# og22.net
KiCad netlist of a schematic drawn in EAGLE
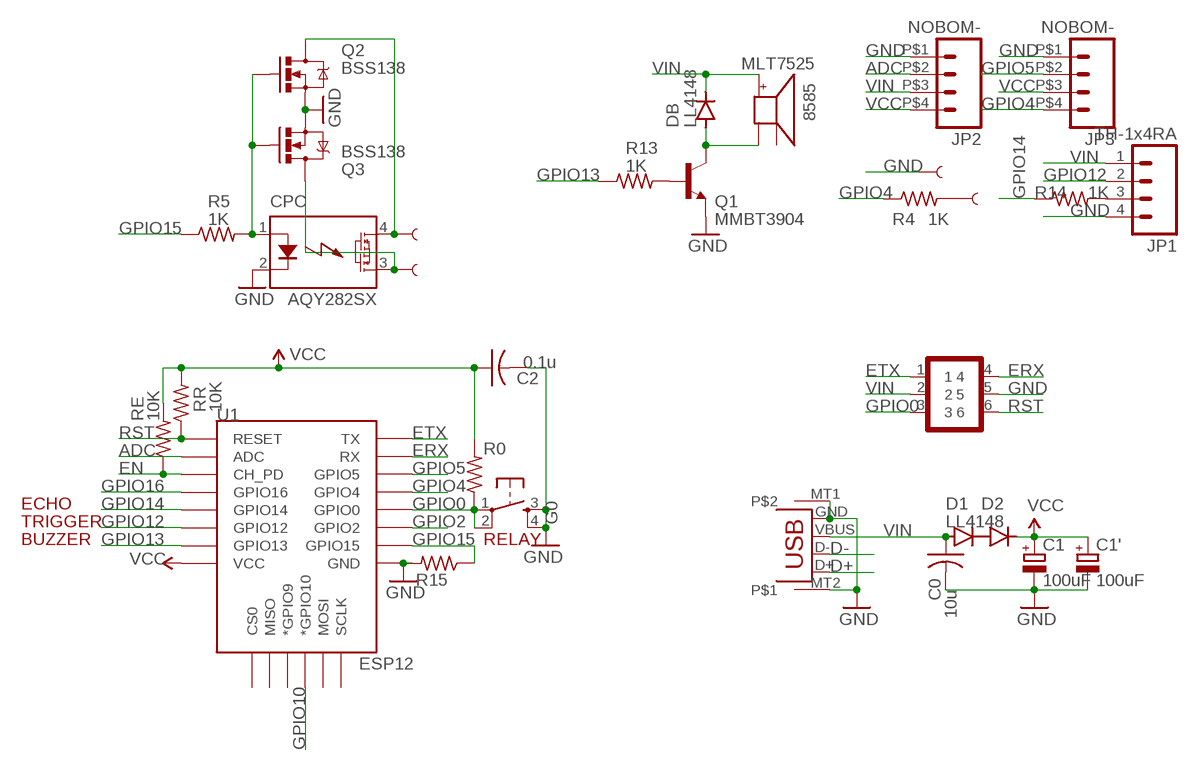
[diagram p0: schematic, sheet 1]

(export (version "E")
  (design (tool "Eeschema 10.0.6"))
  (components
    (comp (ref "8585")
      (value "MLT7525")
      (footprint "eagle-import:SMT-8585-BUZZER")
      (libsource (lib "eagle-import") (part "BUZZER"))
    )
    (comp (ref "C0")
      (value "10u")
      (footprint "eagle-import:C0805K")
      (libsource (lib "eagle-import") (part "C-USC0805K"))
    )
    (comp (ref "C1")
      (value "100uF")
      (footprint "eagle-import:PANASONIC_C")
      (libsource (lib "eagle-import") (part "CPOL-EUC"))
    )
    (comp (ref "C1'")
      (value "100uF")
      (footprint "eagle-import:PANASONIC_C")
      (libsource (lib "eagle-import") (part "CPOL-EUC"))
    )
    (comp (ref "C2")
      (value "0.1u")
      (footprint "eagle-import:C0603K")
      (libsource (lib "eagle-import") (part "C-USC0603K"))
    )
    (comp (ref "CPC")
      (value "AQY282SX")
      (footprint "eagle-import:PHOTOMOS")
      (libsource (lib "eagle-import") (part "AQY282"))
    )
    (comp (ref "D1")
      (value "LL4148")
      (footprint "eagle-import:MINIMELF")
      (libsource (lib "eagle-import") (part "DIODE-MINIMELF"))
    )
    (comp (ref "D2")
      (value "LL4148")
      (footprint "eagle-import:MINIMELF")
      (libsource (lib "eagle-import") (part "DIODE-MINIMELF"))
    )
    (comp (ref "DB")
      (value "LL4148")
      (footprint "eagle-import:MINIMELF")
      (libsource (lib "eagle-import") (part "DIODE-MINIMELF"))
    )
    (comp (ref "G0")
      (value "TH-6x11")
      (footprint "eagle-import:EVQ-Q2")
      (libsource (lib "eagle-import") (part "SPST_TACTEVQQ2"))
    )
    (comp (ref "JP1")
      (value "TH-1x4RA")
      (footprint "eagle-import:1X04_SONICSENSOR_EXT2")
      (libsource (lib "eagle-import") (part "M04EXT2"))
    )
    (comp (ref "JP2")
      (value "NOBOM-")
      (footprint "eagle-import:1X04-2X2")
      (libsource (lib "eagle-import") (part "M042X2"))
    )
    (comp (ref "JP3")
      (value "NOBOM-")
      (footprint "eagle-import:1X04-2X2")
      (libsource (lib "eagle-import") (part "M042X2"))
    )
    (comp (ref "Q1")
      (value "MMBT3904")
      (footprint "eagle-import:SOT23-3")
      (libsource (lib "eagle-import") (part "TRANSISTOR_NPNSOT23-3"))
    )
    (comp (ref "Q2")
      (value "BSS138")
      (footprint "eagle-import:SOT23-3")
      (libsource (lib "eagle-import") (part "MOSFET-NCHANNELSMD"))
    )
    (comp (ref "Q3")
      (value "BSS138")
      (footprint "eagle-import:SOT23-3")
      (libsource (lib "eagle-import") (part "MOSFET-NCHANNELSMD"))
    )
    (comp (ref "R0")
      (value "10K")
      (footprint "eagle-import:R0603")
      (libsource (lib "eagle-import") (part "R-US_R0603"))
    )
    (comp (ref "R4")
      (value "1K")
      (footprint "eagle-import:R0603")
      (libsource (lib "eagle-import") (part "adafruit2013_R-US_R0603"))
    )
    (comp (ref "R5")
      (value "1K")
      (footprint "eagle-import:R0603")
      (libsource (lib "eagle-import") (part "adafruit2013_R-US_R0603"))
    )
    (comp (ref "R13")
      (value "1K")
      (footprint "eagle-import:R0603")
      (libsource (lib "eagle-import") (part "adafruit2013_R-US_R0603"))
    )
    (comp (ref "R14")
      (value "1K")
      (footprint "eagle-import:R0603")
      (libsource (lib "eagle-import") (part "adafruit2013_R-US_R0603"))
    )
    (comp (ref "R15")
      (value "10K")
      (footprint "eagle-import:R0603")
      (libsource (lib "eagle-import") (part "R-US_R0603"))
    )
    (comp (ref "RE")
      (value "10K")
      (footprint "eagle-import:R0603")
      (libsource (lib "eagle-import") (part "R-US_R0603"))
    )
    (comp (ref "RR")
      (value "10K")
      (footprint "eagle-import:R0603")
      (libsource (lib "eagle-import") (part "R-US_R0603"))
    )
    (comp (ref "U$1")
      (value "NOBOM-GF2x3")
      (footprint "eagle-import:GOLDFINGER_2X3")
      (libsource (lib "eagle-import") (part "GOLDFINGER_2X3"))
    )
    (comp (ref "U$2")
      (value "NOBOM-")
      (footprint "eagle-import:PETAL-7MM-DOUBLE")
      (libsource (lib "eagle-import") (part "SEWTAP7MMD"))
    )
    (comp (ref "U$3")
      (value "NOBOM-")
      (footprint "eagle-import:PETAL-7MM-DOUBLE")
      (libsource (lib "eagle-import") (part "SEWTAP7MMD"))
    )
    (comp (ref "U$4")
      (value "NOBOM-")
      (footprint "eagle-import:PETAL-7MM-DOUBLE")
      (libsource (lib "eagle-import") (part "SEWTAP7MMD"))
    )
    (comp (ref "U$5")
      (value "NOBOM-")
      (footprint "eagle-import:PETAL-7MM-DOUBLE")
      (libsource (lib "eagle-import") (part "SEWTAP7MMD"))
    )
    (comp (ref "U1")
      (value "ESP12")
      (footprint "eagle-import:ESP12E-SMD")
      (libsource (lib "eagle-import") (part "ESP12ESMD"))
    )
    (comp (ref "X3")
      (value "MICROXNJ")
      (footprint "eagle-import:USB-MICROB2")
      (libsource (lib "eagle-import") (part "USB+GND"))
    )
  )
  (nets
    (net (code "1") (name "/ADC") (class "Default")
      (node (ref "JP2") (pin "P$2") (pinfunction "2_P$2") (pintype "passive"))
      (node (ref "U1") (pin "ADC") (pinfunction "ADC_ADC") (pintype "bidirectional"))
    )
    (net (code "2") (name "/D+") (class "Default")
      (node (ref "X3") (pin "D+") (pinfunction "D+_D+") (pintype "bidirectional"))
    )
    (net (code "3") (name "/D-") (class "Default")
      (node (ref "X3") (pin "D-") (pinfunction "D-_D-") (pintype "bidirectional"))
    )
    (net (code "4") (name "/EN") (class "Default")
      (node (ref "RE") (pin "1") (pinfunction "1_1") (pintype "passive"))
      (node (ref "U1") (pin "CH_PD") (pinfunction "CH_PD_CH_PD") (pintype "bidirectional"))
    )
    (net (code "5") (name "/ERX") (class "Default")
      (node (ref "U$1") (pin "4") (pinfunction "4_4") (pintype "bidirectional"))
      (node (ref "U1") (pin "RXD0") (pinfunction "RX_RXD0") (pintype "bidirectional"))
    )
    (net (code "6") (name "/ETX") (class "Default")
      (node (ref "U$1") (pin "1") (pinfunction "1_1") (pintype "bidirectional"))
      (node (ref "U1") (pin "TXD0") (pinfunction "TX_TXD0") (pintype "bidirectional"))
    )
    (net (code "7") (name "/GPIO0") (class "Default")
      (node (ref "G0") (pin "1") (pinfunction "1_1") (pintype "passive"))
      (node (ref "G0") (pin "2") (pinfunction "2_2") (pintype "passive"))
      (node (ref "R0") (pin "1") (pinfunction "1_1") (pintype "passive"))
      (node (ref "U$1") (pin "3") (pinfunction "3_3") (pintype "bidirectional"))
      (node (ref "U1") (pin "GPIO0") (pinfunction "GPIO0_GPIO0") (pintype "bidirectional"))
    )
    (net (code "8") (name "/GPIO2") (class "Default")
      (node (ref "U1") (pin "GPIO2") (pinfunction "GPIO2_GPIO2") (pintype "bidirectional"))
    )
    (net (code "9") (name "/GPIO4") (class "Default")
      (node (ref "JP3") (pin "P$4") (pinfunction "4_P$4") (pintype "passive"))
      (node (ref "R4") (pin "1") (pinfunction "1_1") (pintype "passive"))
      (node (ref "U1") (pin "GPIO4") (pinfunction "GPIO4_GPIO4") (pintype "bidirectional"))
    )
    (net (code "10") (name "/GPIO5") (class "Default")
      (node (ref "JP3") (pin "P$2") (pinfunction "2_P$2") (pintype "passive"))
      (node (ref "U1") (pin "GPIO5") (pinfunction "GPIO5_GPIO5") (pintype "bidirectional"))
    )
    (net (code "11") (name "/GPIO10") (class "Default")
      (node (ref "U1") (pin "GPIO10") (pinfunction "*GPIO10_GPIO10") (pintype "bidirectional"))
    )
    (net (code "12") (name "/GPIO12") (class "Default")
      (node (ref "JP1") (pin "2") (pinfunction "2_2") (pintype "passive"))
      (node (ref "U1") (pin "GPIO12") (pinfunction "GPIO12_GPIO12") (pintype "bidirectional"))
    )
    (net (code "13") (name "/GPIO13") (class "Default")
      (node (ref "R13") (pin "1") (pinfunction "1_1") (pintype "passive"))
      (node (ref "U1") (pin "GPIO13") (pinfunction "GPIO13_GPIO13") (pintype "bidirectional"))
    )
    (net (code "14") (name "/GPIO14") (class "Default")
      (node (ref "R14") (pin "1") (pinfunction "1_1") (pintype "passive"))
      (node (ref "U1") (pin "GPIO14") (pinfunction "GPIO14_GPIO14") (pintype "bidirectional"))
    )
    (net (code "15") (name "/GPIO15") (class "Default")
      (node (ref "R15") (pin "1") (pinfunction "1_1") (pintype "passive"))
      (node (ref "R5") (pin "1") (pinfunction "1_1") (pintype "passive"))
      (node (ref "U1") (pin "GPIO15") (pinfunction "GPIO15_GPIO15") (pintype "bidirectional"))
    )
    (net (code "16") (name "/GPIO16") (class "Default")
      (node (ref "U1") (pin "GPIO16") (pinfunction "GPIO16_GPIO16") (pintype "bidirectional"))
    )
    (net (code "17") (name "/RST") (class "Default")
      (node (ref "RR") (pin "1") (pinfunction "1_1") (pintype "passive"))
      (node (ref "U$1") (pin "6") (pinfunction "6_6") (pintype "bidirectional"))
      (node (ref "U1") (pin "RESET") (pinfunction "RESET_RESET") (pintype "bidirectional"))
    )
    (net (code "18") (name "/VIN") (class "Default")
      (node (ref "8585") (pin "+") (pinfunction "+_+") (pintype "passive"))
      (node (ref "C0") (pin "1") (pinfunction "1_1") (pintype "passive"))
      (node (ref "D1") (pin "A") (pinfunction "A_A") (pintype "passive"))
      (node (ref "DB") (pin "C") (pinfunction "C_C") (pintype "passive"))
      (node (ref "JP1") (pin "1") (pinfunction "1_1") (pintype "passive"))
      (node (ref "JP2") (pin "P$3") (pinfunction "3_P$3") (pintype "passive"))
      (node (ref "U$1") (pin "2") (pinfunction "2_2") (pintype "bidirectional"))
      (node (ref "X3") (pin "VBUS") (pinfunction "VBUS_VBUS") (pintype "bidirectional"))
    )
    (net (code "19") (name "GND") (class "Default")
      (node (ref "C0") (pin "2") (pinfunction "2_2") (pintype "passive"))
      (node (ref "C1") (pin "-") (pinfunction "-_-") (pintype "passive"))
      (node (ref "C1'") (pin "-") (pinfunction "-_-") (pintype "passive"))
      (node (ref "C2") (pin "2") (pinfunction "2_2") (pintype "passive"))
      (node (ref "CPC") (pin "2") (pinfunction "K_2") (pintype "passive"))
      (node (ref "G0") (pin "3") (pinfunction "3_3") (pintype "passive"))
      (node (ref "G0") (pin "4") (pinfunction "4_4") (pintype "passive"))
      (node (ref "JP1") (pin "4") (pinfunction "4_4") (pintype "passive"))
      (node (ref "JP2") (pin "P$1") (pinfunction "1_P$1") (pintype "passive"))
      (node (ref "JP3") (pin "P$1") (pinfunction "1_P$1") (pintype "passive"))
      (node (ref "Q1") (pin "2") (pinfunction "E_2") (pintype "passive"))
      (node (ref "Q2") (pin "2") (pinfunction "S_2") (pintype "passive"))
      (node (ref "Q3") (pin "2") (pinfunction "S_2") (pintype "passive"))
      (node (ref "R15") (pin "2") (pinfunction "2_2") (pintype "passive"))
      (node (ref "U$1") (pin "5") (pinfunction "5_5") (pintype "bidirectional"))
      (node (ref "U$4") (pin "P$1") (pinfunction "1_P$1") (pintype "bidirectional"))
      (node (ref "U1") (pin "GND") (pinfunction "GND_GND") (pintype "bidirectional"))
      (node (ref "X3") (pin "GND") (pinfunction "GND_GND") (pintype "bidirectional"))
      (node (ref "X3") (pin "MT1") (pinfunction "P$2_MT1") (pintype "bidirectional"))
      (node (ref "X3") (pin "MT2") (pinfunction "P$1_MT2") (pintype "bidirectional"))
    )
    (net (code "20") (name "Net-(CPC-A)") (class "Default")
      (node (ref "CPC") (pin "1") (pinfunction "A_1") (pintype "passive"))
      (node (ref "Q2") (pin "1") (pinfunction "G_1") (pintype "passive"))
      (node (ref "Q3") (pin "1") (pinfunction "G_1") (pintype "passive"))
      (node (ref "R5") (pin "2") (pinfunction "2_2") (pintype "passive"))
    )
    (net (code "21") (name "Net-(CPC-DS1)") (class "Default")
      (node (ref "CPC") (pin "4") (pinfunction "DS1_4") (pintype "passive"))
      (node (ref "Q2") (pin "3") (pinfunction "D_3") (pintype "passive"))
      (node (ref "U$3") (pin "P$1") (pinfunction "1_P$1") (pintype "bidirectional"))
    )
    (net (code "22") (name "Net-(CPC-DS2)") (class "Default")
      (node (ref "CPC") (pin "3") (pinfunction "DS2_3") (pintype "passive"))
      (node (ref "Q3") (pin "3") (pinfunction "D_3") (pintype "passive"))
      (node (ref "U$2") (pin "P$1") (pinfunction "1_P$1") (pintype "bidirectional"))
    )
    (net (code "23") (name "Net-(D1-PadC)") (class "Default")
      (node (ref "D1") (pin "C") (pinfunction "C_C") (pintype "passive"))
      (node (ref "D2") (pin "A") (pinfunction "A_A") (pintype "passive"))
    )
    (net (code "24") (name "Net-(JP1-Pad3)") (class "Default")
      (node (ref "JP1") (pin "3") (pinfunction "3_3") (pintype "passive"))
      (node (ref "R14") (pin "2") (pinfunction "2_2") (pintype "passive"))
    )
    (net (code "25") (name "Net-(Q1-B)") (class "Default")
      (node (ref "Q1") (pin "1") (pinfunction "B_1") (pintype "passive"))
      (node (ref "R13") (pin "2") (pinfunction "2_2") (pintype "passive"))
    )
    (net (code "26") (name "Net-(Q1-C)") (class "Default")
      (node (ref "8585") (pin "-") (pinfunction "-_-") (pintype "passive"))
      (node (ref "DB") (pin "A") (pinfunction "A_A") (pintype "passive"))
      (node (ref "Q1") (pin "3") (pinfunction "C_3") (pintype "passive"))
    )
    (net (code "27") (name "Net-(U$5-1)") (class "Default")
      (node (ref "R4") (pin "2") (pinfunction "2_2") (pintype "passive"))
      (node (ref "U$5") (pin "P$1") (pinfunction "1_P$1") (pintype "bidirectional"))
    )
    (net (code "28") (name "VCC") (class "Default")
      (node (ref "C1") (pin "+") (pinfunction "+_+") (pintype "passive"))
      (node (ref "C1'") (pin "+") (pinfunction "+_+") (pintype "passive"))
      (node (ref "C2") (pin "1") (pinfunction "1_1") (pintype "passive"))
      (node (ref "D2") (pin "C") (pinfunction "C_C") (pintype "passive"))
      (node (ref "JP2") (pin "P$4") (pinfunction "4_P$4") (pintype "passive"))
      (node (ref "JP3") (pin "P$3") (pinfunction "3_P$3") (pintype "passive"))
      (node (ref "R0") (pin "2") (pinfunction "2_2") (pintype "passive"))
      (node (ref "RE") (pin "2") (pinfunction "2_2") (pintype "passive"))
      (node (ref "RR") (pin "2") (pinfunction "2_2") (pintype "passive"))
      (node (ref "U1") (pin "VCC") (pinfunction "VCC_VCC") (pintype "bidirectional"))
    )
    (net (code "29") (name "unconnected-(8585-PadA-)") (class "Default")
      (node (ref "8585") (pin "A-") (pinfunction "A-_A-") (pintype "passive"))
    )
    (net (code "30") (name "unconnected-(U1-*GPIO9-PadGPIO9)") (class "Default")
      (node (ref "U1") (pin "GPIO9") (pinfunction "*GPIO9_GPIO9") (pintype "bidirectional"))
    )
    (net (code "31") (name "unconnected-(U1-PadCS0)") (class "Default")
      (node (ref "U1") (pin "CS0") (pinfunction "CS0_CS0") (pintype "bidirectional"))
    )
    (net (code "32") (name "unconnected-(U1-PadMISO)") (class "Default")
      (node (ref "U1") (pin "MISO") (pinfunction "MISO_MISO") (pintype "bidirectional"))
    )
    (net (code "33") (name "unconnected-(U1-PadMOSI)") (class "Default")
      (node (ref "U1") (pin "MOSI") (pinfunction "MOSI_MOSI") (pintype "bidirectional"))
    )
    (net (code "34") (name "unconnected-(U1-PadSCLK)") (class "Default")
      (node (ref "U1") (pin "SCLK") (pinfunction "SCLK_SCLK") (pintype "bidirectional"))
    )
  )
)
